# PWM_Outputs.net
KiCad netlist of a schematic drawn in Altium Designer
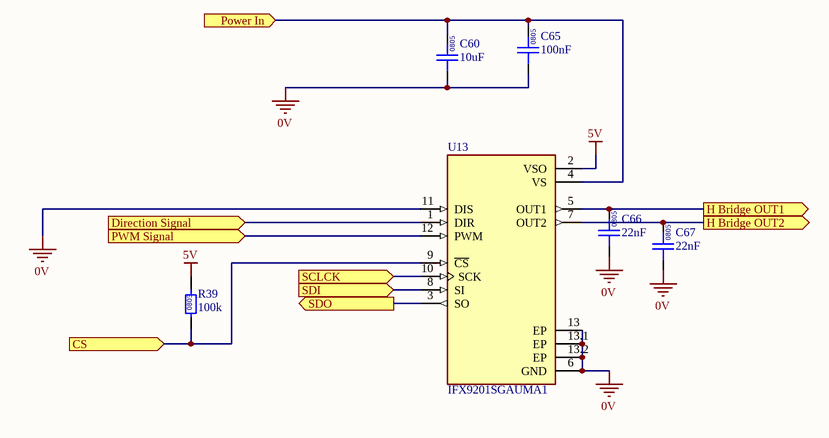
[diagram p0: PWM Outputs.SchDoc]

(export (version "E")
  (design (tool "Eeschema 10.0.6"))
  (components
    (comp (ref "C60")
      (value "10uF")
      (footprint "0805")
      (fields
        (field (name "PART NUMBER") "GRM21BR6YA106KE43L")
        (field (name "MANUFACTURER") "muRata")
        (field (name "TOLERANCE") "10%")
      )
      (libsource (lib "ts_standard_library") (part "Capacitor 0805"))
    )
    (comp (ref "C65")
      (value "100nF")
      (footprint "0805")
      (fields
        (field (name "PART NUMBER") "GCM21BR71H104KA37L")
        (field (name "MANUFACTURER") "muRata")
        (field (name "TOLERANCE") "±10%")
      )
      (libsource (lib "ts_standard_library") (part "Capacitor 0805"))
    )
    (comp (ref "C66")
      (value "22nF")
      (footprint "0805")
      (fields
        (field (name "PART NUMBER") "GCM21B5C1H223JA16L")
        (field (name "MANUFACTURER") "muRata")
        (field (name "TOLERANCE") "±5%")
      )
      (libsource (lib "ts_standard_library") (part "Capacitor 0805"))
    )
    (comp (ref "C67")
      (value "22nF")
      (footprint "0805")
      (fields
        (field (name "PART NUMBER") "GCM21B5C1H223JA16L")
        (field (name "MANUFACTURER") "muRata")
        (field (name "TOLERANCE") "±5%")
      )
      (libsource (lib "ts_standard_library") (part "Capacitor 0805"))
    )
    (comp (ref "R39")
      (value "100k")
      (footprint "0805")
      (fields
        (field (name "PART NUMBER") "RC0805FR07100KL")
        (field (name "MANUFACTURER") "YAGEO")
        (field (name "TOLERANCE") "0.01")
      )
      (libsource (lib "ts_standard_library") (part "Resistor 0805"))
    )
    (comp (ref "U13")
      (value "IFX9201SGAUMA1")
      (footprint "CONV_IFX9201SGAUMA1")
      (description "IC HALF BRIDGE DRIVER 6A 12DSO")
      (fields
        (field (name "MF") "Infineon Technologies")
        (field (name "DIGIKEY PART NUMBER") "IFX9201SGAUMA1TR-ND")
      )
      (libsource (lib "ts_standard_library") (part "IFX9201SGAUMA1"))
    )
  )
  (nets
    (net (code "1") (name "/CS") (class "Default")
      (node (ref "R39") (pin "1") (pinfunction "1_1") (pintype "passive"))
      (node (ref "U13") (pin "9") (pinfunction "~{CS}_9") (pintype "input"))
    )
    (net (code "2") (name "/Direction Signal") (class "Default")
      (node (ref "U13") (pin "1") (pinfunction "DIR_1") (pintype "input"))
    )
    (net (code "3") (name "/H Bridge OUT1") (class "Default")
      (node (ref "C66") (pin "2") (pinfunction "2_2") (pintype "passive"))
      (node (ref "U13") (pin "5") (pinfunction "OUT1_5") (pintype "output"))
    )
    (net (code "4") (name "/H Bridge OUT2") (class "Default")
      (node (ref "C67") (pin "2") (pinfunction "2_2") (pintype "passive"))
      (node (ref "U13") (pin "7") (pinfunction "OUT2_7") (pintype "output"))
    )
    (net (code "5") (name "/PWM Signal") (class "Default")
      (node (ref "U13") (pin "12") (pinfunction "PWM_12") (pintype "input"))
    )
    (net (code "6") (name "/Power In") (class "Default")
      (node (ref "C60") (pin "2") (pinfunction "2_2") (pintype "passive"))
      (node (ref "C65") (pin "2") (pinfunction "2_2") (pintype "passive"))
      (node (ref "U13") (pin "4") (pinfunction "VS_4") (pintype "power_in"))
    )
    (net (code "7") (name "/SCLCK") (class "Default")
      (node (ref "U13") (pin "10") (pinfunction "SCK_10") (pintype "input"))
    )
    (net (code "8") (name "/SDI") (class "Default")
      (node (ref "U13") (pin "8") (pinfunction "SI_8") (pintype "input"))
    )
    (net (code "9") (name "/SDO") (class "Default")
      (node (ref "U13") (pin "3") (pinfunction "SO_3") (pintype "output"))
    )
    (net (code "10") (name "0V") (class "Default")
      (node (ref "C60") (pin "1") (pinfunction "1_1") (pintype "passive"))
      (node (ref "C65") (pin "1") (pinfunction "1_1") (pintype "passive"))
      (node (ref "C66") (pin "1") (pinfunction "1_1") (pintype "passive"))
      (node (ref "C67") (pin "1") (pinfunction "1_1") (pintype "passive"))
      (node (ref "U13") (pin "11") (pinfunction "DIS_11") (pintype "input"))
      (node (ref "U13") (pin "13") (pinfunction "EP_13") (pintype "power_in"))
      (node (ref "U13") (pin "13.1") (pinfunction "EP_13.1") (pintype "power_in"))
      (node (ref "U13") (pin "13.2") (pinfunction "EP_13.2") (pintype "power_in"))
      (node (ref "U13") (pin "6") (pinfunction "GND_6") (pintype "power_in"))
    )
    (net (code "11") (name "5V") (class "Default")
      (node (ref "R39") (pin "2") (pinfunction "2_2") (pintype "passive"))
      (node (ref "U13") (pin "2") (pinfunction "VSO_2") (pintype "power_in"))
    )
  )
)
